# ESP32_Schematic_3.net
KiCad netlist of a schematic drawn in Altium Designer
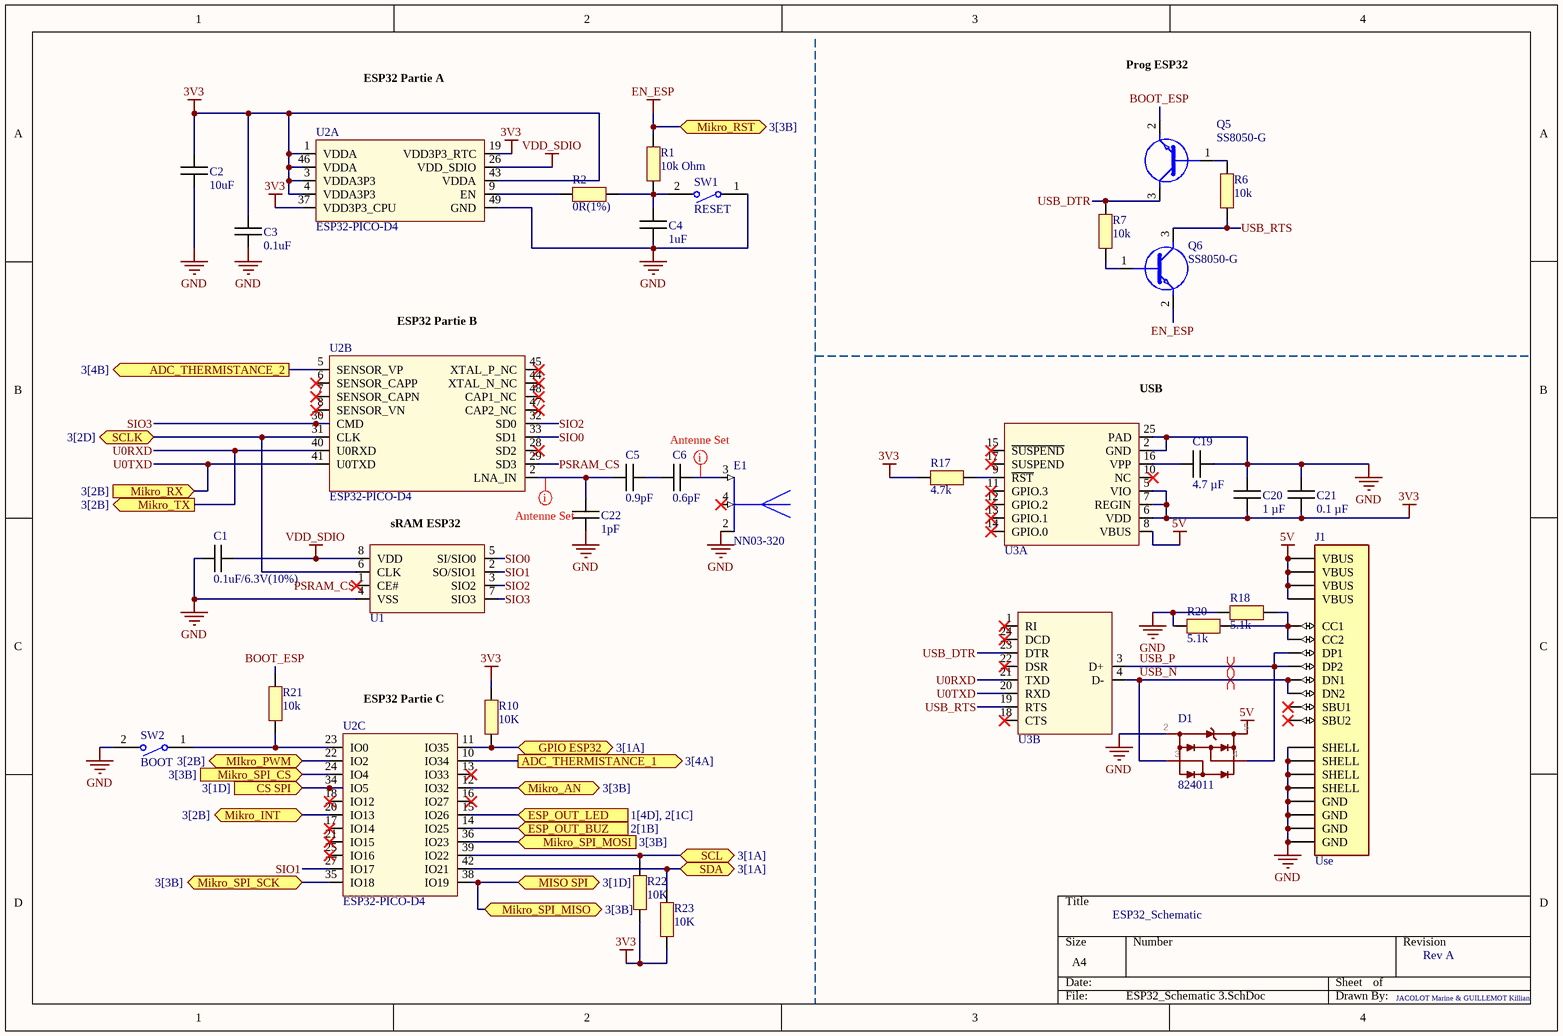
[diagram p0: ESP32_Schematic 3.SchDoc]

(export (version "E")
  (design (tool "Eeschema 10.0.6"))
  (components
    (comp (ref "C1")
      (value "0.1uF/6.3V(10%)")
      (footprint "CAPC1005X06N")
      (libsource (lib "SCHLibrary") (part "Capacitor"))
    )
    (comp (ref "C2")
      (value "10uF")
      (footprint "CAPC1005X06N")
      (libsource (lib "SCHLibrary") (part "Capacitor"))
    )
    (comp (ref "C3")
      (value "0.1uF")
      (footprint "CAPC1005X06N")
      (libsource (lib "SCHLibrary") (part "Capacitor"))
    )
    (comp (ref "C4")
      (value "1uF")
      (footprint "CAPC1005X06N")
      (libsource (lib "SCHLibrary") (part "Capacitor"))
    )
    (comp (ref "C5")
      (value "0.9pF")
      (footprint "CAPC1005X06N")
      (libsource (lib "SCHLibrary") (part "Capacitor"))
    )
    (comp (ref "C6")
      (value "0.6pF")
      (footprint "CAPC1005X06N")
      (libsource (lib "SCHLibrary") (part "Capacitor"))
    )
    (comp (ref "C19")
      (value "4.7 µF")
      (footprint "CAPC1005X06N")
      (libsource (lib "SCHLibrary") (part "Capacitor"))
    )
    (comp (ref "C20")
      (value "1 µF")
      (footprint "CAPC1005X06N")
      (libsource (lib "SCHLibrary") (part "Capacitor"))
    )
    (comp (ref "C21")
      (value "0.1 µF")
      (footprint "CAPC1005X06N")
      (libsource (lib "SCHLibrary") (part "Capacitor"))
    )
    (comp (ref "C22")
      (value "1pF")
      (footprint "CAPC1005X06N")
      (libsource (lib "SCHLibrary") (part "Capacitor"))
    )
    (comp (ref "D1") (value "824011") (footprint "824011") (libsource (lib "SCHLibrary") (part "824011")))
    (comp (ref "E1")
      (value "NN03-320")
      (footprint "XCVR_NN03-320")
      (fields (field (name "MOUSER PART NUMBER") "128-NN03-320"))
      (libsource (lib "SCHLibrary") (part "NN03-320"))
    )
    (comp (ref "J1")
      (value "Use")
      (footprint "USB4085-GF-A")
      (description "Connecteurs USB USB Type C, 2.0, Rec, TH , G/F, RA , Top Mnt, T & R")
      (libsource (lib "SCHLibrary") (part "USB4085-GF-A"))
    )
    (comp (ref "Q5")
      (value "SS8050-G")
      (footprint "SS8050-G")
      (description "Bipolar Transistors - BJT NPN TRANSISTOR 1.5A 40V")
      (libsource (lib "SCHLibrary") (part "SS8050-G"))
    )
    (comp (ref "Q6")
      (value "SS8050-G")
      (footprint "SS8050-G")
      (description "Bipolar Transistors - BJT NPN TRANSISTOR 1.5A 40V")
      (libsource (lib "SCHLibrary") (part "SS8050-G"))
    )
    (comp (ref "R1") (value "10k Ohm") (footprint "RESC1005X06N") (libsource (lib "") (part "Resistor_2")))
    (comp (ref "R2") (value "0R(1%)") (footprint "RESC1005X06N") (libsource (lib "") (part "Resistor_1")))
    (comp (ref "R6")
      (value "10k")
      (footprint "RESC1005X06N")
      (libsource (lib "SCHLibrary") (part "Resistor"))
    )
    (comp (ref "R7") (value "10k") (footprint "RESC1005X06N") (libsource (lib "") (part "Resistor_2")))
    (comp (ref "R10")
      (value "10K")
      (footprint "RESC1005X06N")
      (libsource (lib "SCHLibrary") (part "Resistor"))
    )
    (comp (ref "R17") (value "4.7k") (footprint "RESC1005X06N") (libsource (lib "") (part "Resistor_1")))
    (comp (ref "R18") (value "5.1k") (footprint "RESC1005X06N") (libsource (lib "") (part "Resistor_1")))
    (comp (ref "R20") (value "5.1k") (footprint "RESC1005X06N") (libsource (lib "") (part "Resistor_1")))
    (comp (ref "R21")
      (value "10k")
      (footprint "RESC1005X06N")
      (libsource (lib "SCHLibrary") (part "Resistor"))
    )
    (comp (ref "R22")
      (value "10K")
      (footprint "RESC1005X06N")
      (libsource (lib "SCHLibrary") (part "Resistor"))
    )
    (comp (ref "R23")
      (value "10K")
      (footprint "RESC1005X06N")
      (libsource (lib "SCHLibrary") (part "Resistor"))
    )
    (comp (ref "SW1")
      (value "RESET")
      (footprint "TECO-FSMSM-2_V")
      (description "FSMSM Push Button Switch, 50 mA, -35 to 85 degC, 2-Pin SMD, RoHS, Bulk")
      (fields (field (name "MANUFACTURER") "TE Connectivity"))
      (libsource (lib "SCHLibrary") (part "CMP-2000-07511-1"))
    )
    (comp (ref "SW2")
      (value "BOOT")
      (footprint "TECO-FSMSM-2_V")
      (description "FSMSM Push Button Switch, 50 mA, -35 to 85 degC, 2-Pin SMD, RoHS, Bulk")
      (fields (field (name "MANUFACTURER") "TE Connectivity"))
      (libsource (lib "SCHLibrary") (part "CMP-2000-07511-1"))
    )
    (comp (ref "U1")
      (value "IS66WVS1M8BLL-104NLI")
      (footprint "SOIC127P600X175-8N")
      (description "SRAM 8Mb, SerialRAM, 2.7V-3.6V, 104MHz, 8 pin SOIC 150 mil, RoHS")
      (libsource (lib "SCHLibrary") (part "SRAM"))
    )
    (comp (ref "U2")
      (value "ESP32-PICO-D4")
      (footprint "PQFN50P700X700X104_HS-49N")
      (libsource (lib "SCHLibrary") (part "ESP32"))
    )
    (comp (ref "U3")
      (value "CP2104-F03-GM")
      (footprint "PQFN50P400X400X80_HS-25N")
      (description "USB Bridge, USB to UART USB 2.0 UART Interface 24-QFN (4x4)")
      (libsource (lib "SCHLibrary") (part "USBBridge"))
    )
  )
  (nets
    (net (code "1") (name "/ADC_THERMISTANCE_1") (class "Default")
      (node (ref "U2") (pin "10") (pinfunction "IO34_10") (pintype "passive"))
    )
    (net (code "2") (name "/ADC_THERMISTANCE_2") (class "Default")
      (node (ref "U2") (pin "5") (pinfunction "SENSOR_VP_5") (pintype "passive"))
    )
    (net (code "3") (name "/BOOT_ESP") (class "Default")
      (node (ref "Q5") (pin "2") (pinfunction "E_2") (pintype "passive"))
      (node (ref "R21") (pin "2") (pinfunction "2_2") (pintype "passive"))
    )
    (net (code "4") (name "/CS SPI") (class "Default")
      (node (ref "U2") (pin "34") (pinfunction "IO5_34") (pintype "passive"))
    )
    (net (code "5") (name "/ESP_OUT_BUZ") (class "Default")
      (node (ref "U2") (pin "14") (pinfunction "IO25_14") (pintype "passive"))
    )
    (net (code "6") (name "/ESP_OUT_LED") (class "Default")
      (node (ref "U2") (pin "15") (pinfunction "IO26_15") (pintype "passive"))
    )
    (net (code "7") (name "/GPIO ESP32") (class "Default")
      (node (ref "R10") (pin "1") (pinfunction "1_1") (pintype "passive"))
      (node (ref "U2") (pin "11") (pinfunction "IO35_11") (pintype "passive"))
    )
    (net (code "8") (name "/MISO SPI") (class "Default")
      (node (ref "U2") (pin "38") (pinfunction "IO19_38") (pintype "passive"))
    )
    (net (code "9") (name "/MIkro_PWM") (class "Default")
      (node (ref "U2") (pin "22") (pinfunction "IO2_22") (pintype "passive"))
    )
    (net (code "10") (name "/Mikro_AN") (class "Default")
      (node (ref "U2") (pin "12") (pinfunction "IO32_12") (pintype "passive"))
    )
    (net (code "11") (name "/Mikro_INT") (class "Default")
      (node (ref "U2") (pin "20") (pinfunction "IO13_20") (pintype "passive"))
    )
    (net (code "12") (name "/Mikro_SPI_CS") (class "Default")
      (node (ref "U2") (pin "24") (pinfunction "IO4_24") (pintype "passive"))
    )
    (net (code "13") (name "/Mikro_SPI_MOSI") (class "Default")
      (node (ref "U2") (pin "36") (pinfunction "IO23_36") (pintype "passive"))
    )
    (net (code "14") (name "/Mikro_SPI_SCK") (class "Default")
      (node (ref "U2") (pin "35") (pinfunction "IO18_35") (pintype "passive"))
    )
    (net (code "15") (name "/PSRAM_CS") (class "Default")
      (node (ref "U1") (pin "1") (pinfunction "CE#_1") (pintype "passive"))
      (node (ref "U2") (pin "29") (pinfunction "SD3_29") (pintype "passive"))
    )
    (net (code "16") (name "/SCL") (class "Default")
      (node (ref "R22") (pin "2") (pinfunction "2_2") (pintype "passive"))
      (node (ref "U2") (pin "39") (pinfunction "IO22_39") (pintype "passive"))
    )
    (net (code "17") (name "/SCLK") (class "Default")
      (node (ref "U1") (pin "6") (pinfunction "CLK_6") (pintype "passive"))
      (node (ref "U2") (pin "31") (pinfunction "CLK_31") (pintype "passive"))
    )
    (net (code "18") (name "/SDA") (class "Default")
      (node (ref "R23") (pin "2") (pinfunction "2_2") (pintype "passive"))
      (node (ref "U2") (pin "42") (pinfunction "IO21_42") (pintype "passive"))
    )
    (net (code "19") (name "/SIO0") (class "Default")
      (node (ref "U1") (pin "5") (pinfunction "SI/SIO0_5") (pintype "passive"))
      (node (ref "U2") (pin "33") (pinfunction "SD1_33") (pintype "passive"))
    )
    (net (code "20") (name "/SIO1") (class "Default")
      (node (ref "U1") (pin "2") (pinfunction "SO/SIO1_2") (pintype "passive"))
      (node (ref "U2") (pin "27") (pinfunction "IO17_27") (pintype "passive"))
    )
    (net (code "21") (name "/SIO2") (class "Default")
      (node (ref "U1") (pin "3") (pinfunction "SIO2_3") (pintype "passive"))
      (node (ref "U2") (pin "32") (pinfunction "SD0_32") (pintype "passive"))
    )
    (net (code "22") (name "/SIO3") (class "Default")
      (node (ref "U1") (pin "7") (pinfunction "SIO3_7") (pintype "passive"))
      (node (ref "U2") (pin "30") (pinfunction "CMD_30") (pintype "passive"))
    )
    (net (code "23") (name "/U0RXD") (class "Default")
      (node (ref "U2") (pin "40") (pinfunction "U0RXD_40") (pintype "passive"))
      (node (ref "U3") (pin "21") (pinfunction "TXD_21") (pintype "passive"))
    )
    (net (code "24") (name "/U0TXD") (class "Default")
      (node (ref "U2") (pin "41") (pinfunction "U0TXD_41") (pintype "passive"))
      (node (ref "U3") (pin "20") (pinfunction "RXD_20") (pintype "passive"))
    )
    (net (code "25") (name "/USB_DTR") (class "Default")
      (node (ref "Q5") (pin "3") (pinfunction "C_3") (pintype "passive"))
      (node (ref "R7") (pin "1") (pinfunction "1_1") (pintype "passive"))
      (node (ref "U3") (pin "23") (pinfunction "DTR_23") (pintype "passive"))
    )
    (net (code "26") (name "/USB_N") (class "Default")
      (node (ref "D1") (pin "3") (pinfunction "1_3") (pintype "passive"))
      (node (ref "J1") (pin "A7") (pinfunction "DN1_A7") (pintype "bidirectional"))
      (node (ref "J1") (pin "B7") (pinfunction "DN2_B7") (pintype "bidirectional"))
      (node (ref "U3") (pin "4") (pinfunction "D-_4") (pintype "passive"))
    )
    (net (code "27") (name "/USB_P") (class "Default")
      (node (ref "D1") (pin "4") (pinfunction "2_4") (pintype "passive"))
      (node (ref "J1") (pin "A6") (pinfunction "DP1_A6") (pintype "bidirectional"))
      (node (ref "J1") (pin "B6") (pinfunction "DP2_B6") (pintype "bidirectional"))
      (node (ref "U3") (pin "3") (pinfunction "D+_3") (pintype "passive"))
    )
    (net (code "28") (name "/USB_RTS") (class "Default")
      (node (ref "Q6") (pin "3") (pinfunction "C_3") (pintype "passive"))
      (node (ref "R6") (pin "1") (pinfunction "1_1") (pintype "passive"))
      (node (ref "U3") (pin "19") (pinfunction "RTS_19") (pintype "passive"))
    )
    (net (code "29") (name "3V3") (class "Default")
      (node (ref "C2") (pin "1") (pinfunction "1_1") (pintype "passive"))
      (node (ref "C20") (pin "2") (pinfunction "2_2") (pintype "passive"))
      (node (ref "C21") (pin "1") (pinfunction "1_1") (pintype "passive"))
      (node (ref "C3") (pin "1") (pinfunction "1_1") (pintype "passive"))
      (node (ref "R10") (pin "2") (pinfunction "2_2") (pintype "passive"))
      (node (ref "R17") (pin "1") (pinfunction "1_1") (pintype "passive"))
      (node (ref "R22") (pin "1") (pinfunction "1_1") (pintype "passive"))
      (node (ref "R23") (pin "1") (pinfunction "1_1") (pintype "passive"))
      (node (ref "U2") (pin "1") (pinfunction "VDDA_1") (pintype "passive"))
      (node (ref "U2") (pin "19") (pinfunction "VDD3P3_RTC_19") (pintype "passive"))
      (node (ref "U2") (pin "3") (pinfunction "VDDA3P3_3") (pintype "passive"))
      (node (ref "U2") (pin "37") (pinfunction "VDD3P3_CPU_37") (pintype "passive"))
      (node (ref "U2") (pin "4") (pinfunction "VDDA3P3_4") (pintype "passive"))
      (node (ref "U2") (pin "43") (pinfunction "VDDA_43") (pintype "passive"))
      (node (ref "U2") (pin "46") (pinfunction "VDDA_46") (pintype "passive"))
      (node (ref "U3") (pin "5") (pinfunction "VIO_5") (pintype "passive"))
      (node (ref "U3") (pin "6") (pinfunction "VDD_6") (pintype "passive"))
      (node (ref "U3") (pin "7") (pinfunction "REGIN_7") (pintype "passive"))
    )
    (net (code "30") (name "5V") (class "Default")
      (node (ref "D1") (pin "5") (pinfunction "VDD_5") (pintype "power_in"))
      (node (ref "J1") (pin "A4") (pinfunction "VBUS_A4") (pintype "power_in"))
      (node (ref "J1") (pin "A9") (pinfunction "VBUS_A9") (pintype "power_in"))
      (node (ref "J1") (pin "B4") (pinfunction "VBUS_B4") (pintype "power_in"))
      (node (ref "J1") (pin "B9") (pinfunction "VBUS_B9") (pintype "power_in"))
      (node (ref "U3") (pin "8") (pinfunction "VBUS_8") (pintype "passive"))
    )
    (net (code "31") (name "EN_ESP") (class "Default")
      (node (ref "Q6") (pin "2") (pinfunction "E_2") (pintype "passive"))
      (node (ref "R1") (pin "1") (pinfunction "1_1") (pintype "passive"))
    )
    (net (code "32") (name "GND") (class "Default")
      (node (ref "C1") (pin "1") (pinfunction "1_1") (pintype "passive"))
      (node (ref "C19") (pin "2") (pinfunction "2_2") (pintype "passive"))
      (node (ref "C2") (pin "2") (pinfunction "2_2") (pintype "passive"))
      (node (ref "C20") (pin "1") (pinfunction "1_1") (pintype "passive"))
      (node (ref "C21") (pin "2") (pinfunction "2_2") (pintype "passive"))
      (node (ref "C22") (pin "2") (pinfunction "2_2") (pintype "passive"))
      (node (ref "C3") (pin "2") (pinfunction "2_2") (pintype "passive"))
      (node (ref "C4") (pin "2") (pinfunction "2_2") (pintype "passive"))
      (node (ref "D1") (pin "2") (pinfunction "GND_2") (pintype "power_in"))
      (node (ref "E1") (pin "2") (pinfunction "GROUND_2") (pintype "power_in"))
      (node (ref "J1") (pin "A1") (pinfunction "GND_A1") (pintype "power_in"))
      (node (ref "J1") (pin "A12") (pinfunction "GND_A12") (pintype "power_in"))
      (node (ref "J1") (pin "B1") (pinfunction "GND_B1") (pintype "power_in"))
      (node (ref "J1") (pin "B12") (pinfunction "GND_B12") (pintype "power_in"))
      (node (ref "J1") (pin "S1") (pinfunction "SHELL_S1") (pintype "passive"))
      (node (ref "J1") (pin "S2") (pinfunction "SHELL_S2") (pintype "passive"))
      (node (ref "J1") (pin "S3") (pinfunction "SHELL_S3") (pintype "passive"))
      (node (ref "J1") (pin "S4") (pinfunction "SHELL_S4") (pintype "passive"))
      (node (ref "R18") (pin "1") (pinfunction "1_1") (pintype "passive"))
      (node (ref "R20") (pin "1") (pinfunction "1_1") (pintype "passive"))
      (node (ref "SW1") (pin "1") (pinfunction "1_1") (pintype "passive"))
      (node (ref "SW2") (pin "2") (pinfunction "2_2") (pintype "passive"))
      (node (ref "U1") (pin "4") (pinfunction "VSS_4") (pintype "passive"))
      (node (ref "U2") (pin "49") (pinfunction "GND_49") (pintype "passive"))
      (node (ref "U3") (pin "2") (pinfunction "GND_2") (pintype "passive"))
      (node (ref "U3") (pin "25") (pinfunction "PAD_25") (pintype "passive"))
    )
    (net (code "33") (name "Net-(C4-Pad1)") (class "Default")
      (node (ref "C4") (pin "1") (pinfunction "1_1") (pintype "passive"))
      (node (ref "R1") (pin "2") (pinfunction "2_2") (pintype "passive"))
      (node (ref "R2") (pin "2") (pinfunction "2_2") (pintype "passive"))
      (node (ref "SW1") (pin "2") (pinfunction "2_2") (pintype "passive"))
    )
    (net (code "34") (name "Net-(C5-Pad2)") (class "Default")
      (node (ref "C5") (pin "2") (pinfunction "2_2") (pintype "passive"))
      (node (ref "C6") (pin "1") (pinfunction "1_1") (pintype "passive"))
    )
    (net (code "35") (name "Net-(E1-FEED_BLUETOOTH)") (class "Default")
      (node (ref "C6") (pin "2") (pinfunction "2_2") (pintype "passive"))
      (node (ref "E1") (pin "3") (pinfunction "FEED_BLUETOOTH_3") (pintype "input"))
    )
    (net (code "36") (name "Net-(J1-CC1)") (class "Default")
      (node (ref "J1") (pin "A5") (pinfunction "CC1_A5") (pintype "bidirectional"))
      (node (ref "J1") (pin "B5") (pinfunction "CC2_B5") (pintype "bidirectional"))
      (node (ref "R18") (pin "2") (pinfunction "2_2") (pintype "passive"))
      (node (ref "R20") (pin "2") (pinfunction "2_2") (pintype "passive"))
    )
    (net (code "37") (name "Net-(Q5-B)") (class "Default")
      (node (ref "Q5") (pin "1") (pinfunction "B_1") (pintype "passive"))
      (node (ref "R6") (pin "2") (pinfunction "2_2") (pintype "passive"))
    )
    (net (code "38") (name "Net-(Q6-B)") (class "Default")
      (node (ref "Q6") (pin "1") (pinfunction "B_1") (pintype "passive"))
      (node (ref "R7") (pin "2") (pinfunction "2_2") (pintype "passive"))
    )
    (net (code "39") (name "Net-(U2A-EN)") (class "Default")
      (node (ref "R2") (pin "1") (pinfunction "1_1") (pintype "passive"))
      (node (ref "U2") (pin "9") (pinfunction "EN_9") (pintype "passive"))
    )
    (net (code "40") (name "Net-(U2B-LNA_IN)") (class "Default")
      (node (ref "C22") (pin "1") (pinfunction "1_1") (pintype "passive"))
      (node (ref "C5") (pin "1") (pinfunction "1_1") (pintype "passive"))
      (node (ref "U2") (pin "2") (pinfunction "LNA_IN_2") (pintype "passive"))
    )
    (net (code "41") (name "Net-(U2C-IO0)") (class "Default")
      (node (ref "R21") (pin "1") (pinfunction "1_1") (pintype "passive"))
      (node (ref "SW2") (pin "1") (pinfunction "1_1") (pintype "passive"))
      (node (ref "U2") (pin "23") (pinfunction "IO0_23") (pintype "passive"))
    )
    (net (code "42") (name "Net-(U3A-VPP)") (class "Default")
      (node (ref "C19") (pin "1") (pinfunction "1_1") (pintype "passive"))
      (node (ref "U3") (pin "16") (pinfunction "VPP_16") (pintype "passive"))
    )
    (net (code "43") (name "Net-(U3A-~{RST})") (class "Default")
      (node (ref "R17") (pin "2") (pinfunction "2_2") (pintype "passive"))
      (node (ref "U3") (pin "9") (pinfunction "~{RST}_9") (pintype "passive"))
    )
    (net (code "44") (name "VDD_SDIO") (class "Default")
      (node (ref "C1") (pin "2") (pinfunction "2_2") (pintype "passive"))
      (node (ref "U1") (pin "8") (pinfunction "VDD_8") (pintype "passive"))
      (node (ref "U2") (pin "26") (pinfunction "VDD_SDIO_26") (pintype "passive"))
    )
    (net (code "45") (name "unconnected-(E1-FEED_GNSS-Pad4)") (class "Default")
      (node (ref "E1") (pin "4") (pinfunction "FEED_GNSS_4") (pintype "input+no_connect"))
    )
    (net (code "46") (name "unconnected-(J1-SBU1-PadA8)") (class "Default")
      (node (ref "J1") (pin "A8") (pinfunction "SBU1_A8") (pintype "bidirectional+no_connect"))
    )
    (net (code "47") (name "unconnected-(J1-SBU2-PadB8)") (class "Default")
      (node (ref "J1") (pin "B8") (pinfunction "SBU2_B8") (pintype "bidirectional+no_connect"))
    )
    (net (code "48") (name "unconnected-(U2B-CAP1_NC-Pad48)") (class "Default")
      (node (ref "U2") (pin "48") (pinfunction "CAP1_NC_48") (pintype "passive+no_connect"))
    )
    (net (code "49") (name "unconnected-(U2B-CAP2_NC-Pad47)") (class "Default")
      (node (ref "U2") (pin "47") (pinfunction "CAP2_NC_47") (pintype "passive+no_connect"))
    )
    (net (code "50") (name "unconnected-(U2B-SD2-Pad28)") (class "Default")
      (node (ref "U2") (pin "28") (pinfunction "SD2_28") (pintype "passive+no_connect"))
    )
    (net (code "51") (name "unconnected-(U2B-SENSOR_CAPN-Pad7)") (class "Default")
      (node (ref "U2") (pin "7") (pinfunction "SENSOR_CAPN_7") (pintype "passive+no_connect"))
    )
    (net (code "52") (name "unconnected-(U2B-SENSOR_CAPP-Pad6)") (class "Default")
      (node (ref "U2") (pin "6") (pinfunction "SENSOR_CAPP_6") (pintype "passive+no_connect"))
    )
    (net (code "53") (name "unconnected-(U2B-SENSOR_VN-Pad8)") (class "Default")
      (node (ref "U2") (pin "8") (pinfunction "SENSOR_VN_8") (pintype "passive+no_connect"))
    )
    (net (code "54") (name "unconnected-(U2B-XTAL_N_NC-Pad44)") (class "Default")
      (node (ref "U2") (pin "44") (pinfunction "XTAL_N_NC_44") (pintype "passive+no_connect"))
    )
    (net (code "55") (name "unconnected-(U2B-XTAL_P_NC-Pad45)") (class "Default")
      (node (ref "U2") (pin "45") (pinfunction "XTAL_P_NC_45") (pintype "passive+no_connect"))
    )
    (net (code "56") (name "unconnected-(U2C-IO12-Pad18)") (class "Default")
      (node (ref "U2") (pin "18") (pinfunction "IO12_18") (pintype "passive+no_connect"))
    )
    (net (code "57") (name "unconnected-(U2C-IO14-Pad17)") (class "Default")
      (node (ref "U2") (pin "17") (pinfunction "IO14_17") (pintype "passive+no_connect"))
    )
    (net (code "58") (name "unconnected-(U2C-IO15-Pad21)") (class "Default")
      (node (ref "U2") (pin "21") (pinfunction "IO15_21") (pintype "passive+no_connect"))
    )
    (net (code "59") (name "unconnected-(U2C-IO16-Pad25)") (class "Default")
      (node (ref "U2") (pin "25") (pinfunction "IO16_25") (pintype "passive+no_connect"))
    )
    (net (code "60") (name "unconnected-(U2C-IO27-Pad16)") (class "Default")
      (node (ref "U2") (pin "16") (pinfunction "IO27_16") (pintype "passive+no_connect"))
    )
    (net (code "61") (name "unconnected-(U2C-IO33-Pad13)") (class "Default")
      (node (ref "U2") (pin "13") (pinfunction "IO33_13") (pintype "passive+no_connect"))
    )
    (net (code "62") (name "unconnected-(U3A-GPIO.0-Pad14)") (class "Default")
      (node (ref "U3") (pin "14") (pinfunction "GPIO.0_14") (pintype "passive+no_connect"))
    )
    (net (code "63") (name "unconnected-(U3A-GPIO.1-Pad13)") (class "Default")
      (node (ref "U3") (pin "13") (pinfunction "GPIO.1_13") (pintype "passive+no_connect"))
    )
    (net (code "64") (name "unconnected-(U3A-GPIO.2-Pad12)") (class "Default")
      (node (ref "U3") (pin "12") (pinfunction "GPIO.2_12") (pintype "passive+no_connect"))
    )
    (net (code "65") (name "unconnected-(U3A-GPIO.3-Pad11)") (class "Default")
      (node (ref "U3") (pin "11") (pinfunction "GPIO.3_11") (pintype "passive+no_connect"))
    )
    (net (code "66") (name "unconnected-(U3A-NC-Pad10)") (class "Default")
      (node (ref "U3") (pin "10") (pinfunction "NC_10") (pintype "passive+no_connect"))
    )
    (net (code "67") (name "unconnected-(U3A-SUSPEND-Pad17)") (class "Default")
      (node (ref "U3") (pin "17") (pinfunction "SUSPEND_17") (pintype "passive+no_connect"))
    )
    (net (code "68") (name "unconnected-(U3A-~{SUSPEND}-Pad15)") (class "Default")
      (node (ref "U3") (pin "15") (pinfunction "~{SUSPEND}_15") (pintype "passive+no_connect"))
    )
    (net (code "69") (name "unconnected-(U3B-CTS-Pad18)") (class "Default")
      (node (ref "U3") (pin "18") (pinfunction "CTS_18") (pintype "passive+no_connect"))
    )
    (net (code "70") (name "unconnected-(U3B-DCD-Pad24)") (class "Default")
      (node (ref "U3") (pin "24") (pinfunction "DCD_24") (pintype "passive+no_connect"))
    )
    (net (code "71") (name "unconnected-(U3B-DSR-Pad22)") (class "Default")
      (node (ref "U3") (pin "22") (pinfunction "DSR_22") (pintype "passive+no_connect"))
    )
    (net (code "72") (name "unconnected-(U3B-RI-Pad1)") (class "Default")
      (node (ref "U3") (pin "1") (pinfunction "RI_1") (pintype "passive+no_connect"))
    )
  )
)
